# giraffe12.net
KiCad netlist of a schematic drawn in EAGLE
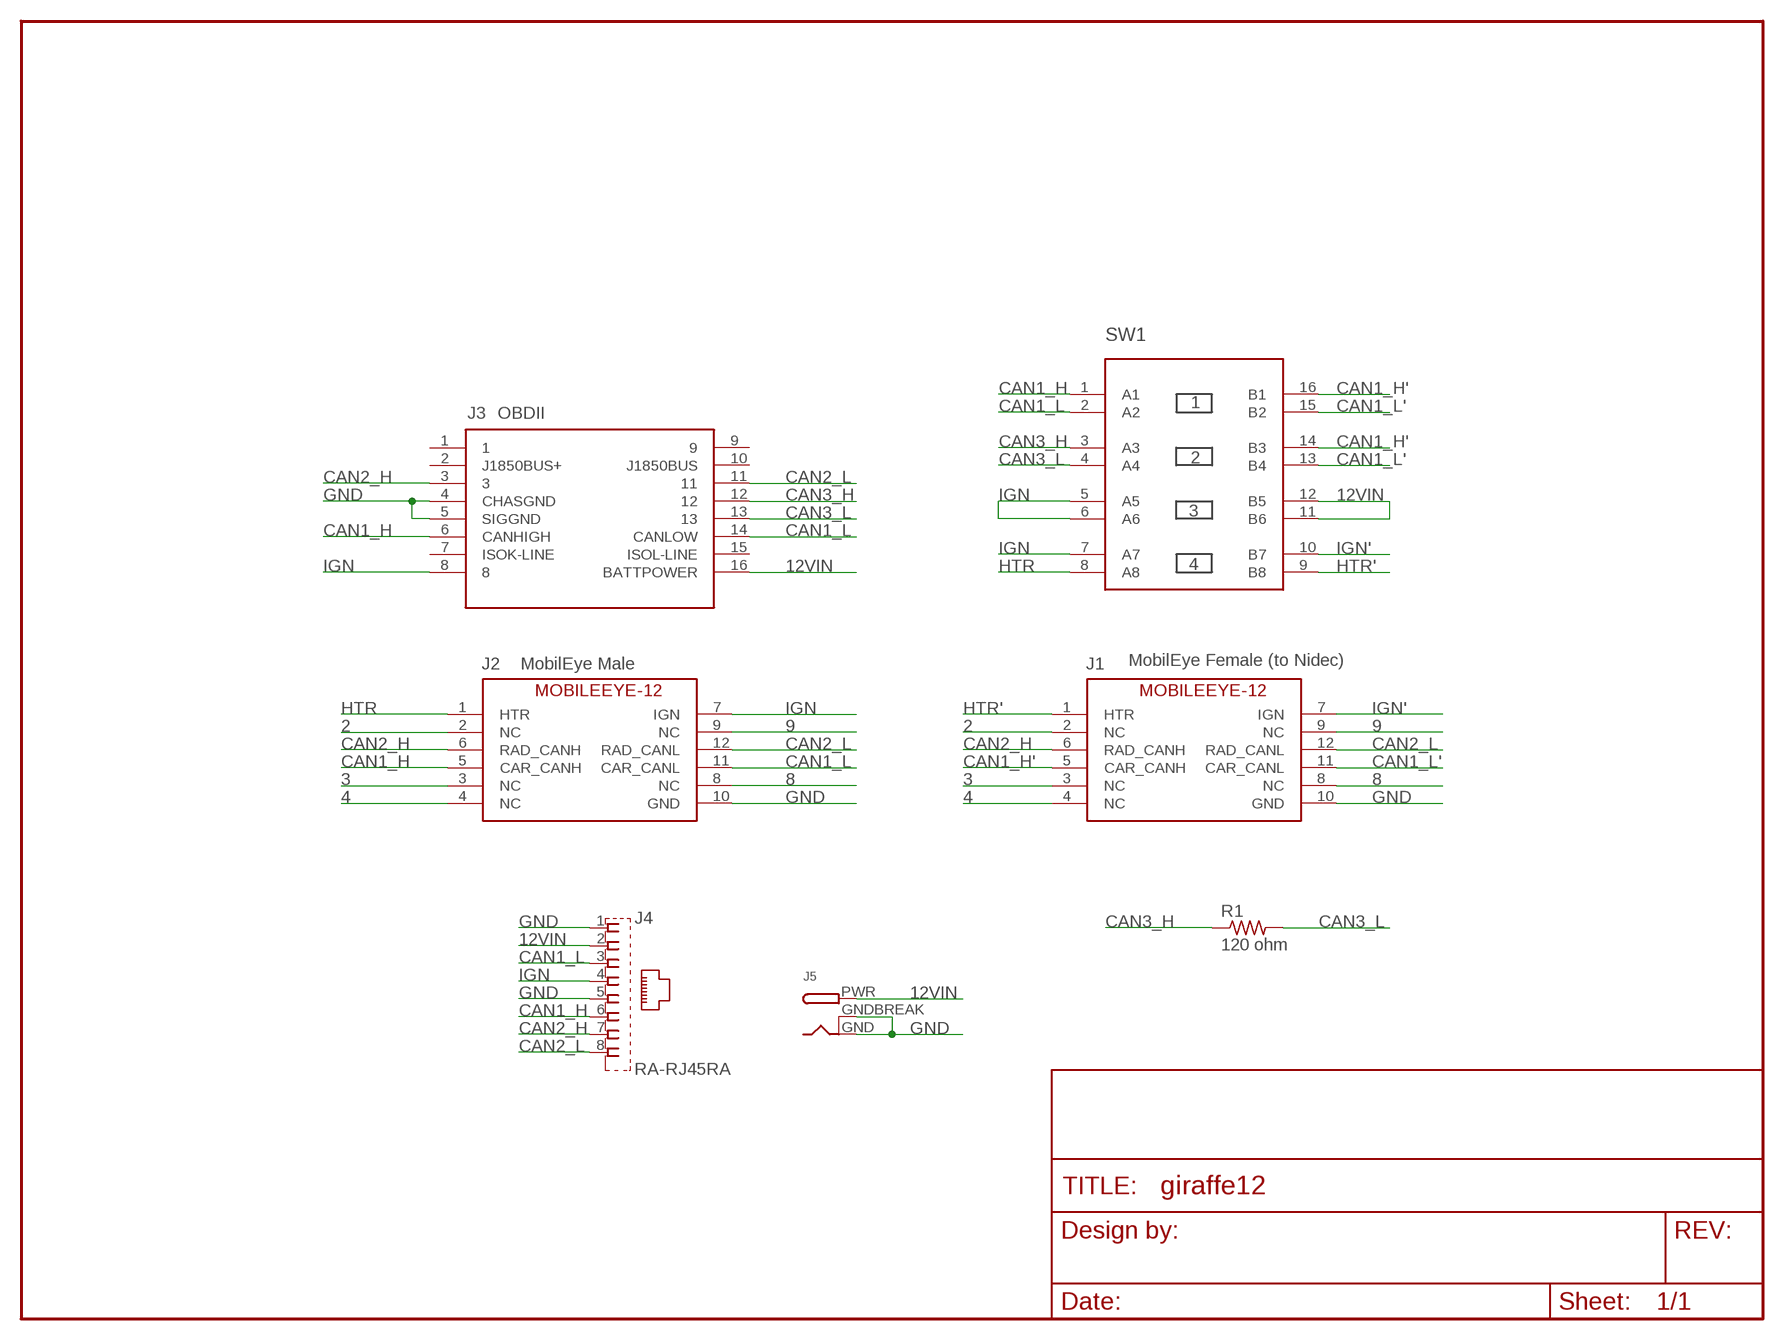
[diagram p0: schematic, sheet 1]

(export (version "E")
  (design (tool "Eeschema 10.0.6"))
  (components
    (comp (ref "FRAME1")
      (value "FRAME-LETTERNO_PACKAGE")
      (footprint "eagle-import:DUMMY")
      (fields (field (name "DESIGNER") "Nobody"))
      (libsource (lib "eagle-import") (part "FRAME-LETTERNO_PACKAGE"))
    )
    (comp (ref "J1")
      (value "MOBILEEYE-12FEMALE")
      (footprint "eagle-import:2X6-TE-FEMALE")
      (libsource (lib "eagle-import") (part "MOBILEEYE-12FEMALE"))
    )
    (comp (ref "J2")
      (value "MOBILEEYE-12MALE")
      (footprint "eagle-import:2X6-TE-RA")
      (libsource (lib "eagle-import") (part "MOBILEEYE-12MALE"))
    )
    (comp (ref "J3")
      (value "OBDII-FEMALE-CUT")
      (footprint "eagle-import:OBDII-FEMALE-MIDCUT")
      (libsource (lib "eagle-import") (part "OBDII-FEMALE-CUT"))
    )
    (comp (ref "J4")
      (value "RA-RJ45RA")
      (footprint "eagle-import:RA-RJ45")
      (libsource (lib "eagle-import") (part "RA-RJ45RA"))
    )
    (comp (ref "J5")
      (value "DCBARRELPTH")
      (footprint "eagle-import:DCJACK_2MM_PTH")
      (libsource (lib "eagle-import") (part "DCBARRELPTH"))
    )
    (comp (ref "R1")
      (value "120 ohm")
      (footprint "eagle-import:0603-R")
      (libsource (lib "eagle-import") (part "R0603"))
    )
    (comp (ref "SW1")
      (value "4XDPSTSMT")
      (footprint "eagle-import:4-DPST")
      (libsource (lib "eagle-import") (part "4XDPSTSMT"))
    )
  )
  (nets
    (net (code "1") (name "/2") (class "Default")
      (node (ref "J1") (pin "2") (pinfunction "NC_2") (pintype "bidirectional"))
      (node (ref "J2") (pin "2") (pinfunction "NC_2") (pintype "bidirectional"))
    )
    (net (code "2") (name "/3") (class "Default")
      (node (ref "J1") (pin "3") (pinfunction "NC_3") (pintype "bidirectional"))
      (node (ref "J2") (pin "3") (pinfunction "NC_3") (pintype "bidirectional"))
    )
    (net (code "3") (name "/4") (class "Default")
      (node (ref "J1") (pin "4") (pinfunction "NC_4") (pintype "bidirectional"))
      (node (ref "J2") (pin "4") (pinfunction "NC_4") (pintype "bidirectional"))
    )
    (net (code "4") (name "/8") (class "Default")
      (node (ref "J1") (pin "8") (pinfunction "NC_8") (pintype "bidirectional"))
      (node (ref "J2") (pin "8") (pinfunction "NC_8") (pintype "bidirectional"))
    )
    (net (code "5") (name "/9") (class "Default")
      (node (ref "J1") (pin "9") (pinfunction "NC_9") (pintype "bidirectional"))
      (node (ref "J2") (pin "9") (pinfunction "NC_9") (pintype "bidirectional"))
    )
    (net (code "6") (name "/12VIN") (class "Default")
      (node (ref "J3") (pin "16") (pinfunction "BATTPOWER_16") (pintype "bidirectional"))
      (node (ref "J4") (pin "2") (pinfunction "2_2") (pintype "passive"))
      (node (ref "J5") (pin "PWR") (pinfunction "PWR_PWR") (pintype "power_in"))
      (node (ref "SW1") (pin "11") (pinfunction "B6_11") (pintype "bidirectional"))
      (node (ref "SW1") (pin "12") (pinfunction "B5_12") (pintype "bidirectional"))
    )
    (net (code "7") (name "/CAN1_H") (class "Default")
      (node (ref "J2") (pin "5") (pinfunction "CAR_CANH_5") (pintype "bidirectional"))
      (node (ref "J3") (pin "6") (pinfunction "CANHIGH_6") (pintype "bidirectional"))
      (node (ref "J4") (pin "6") (pinfunction "6_6") (pintype "passive"))
      (node (ref "SW1") (pin "1") (pinfunction "A1_1") (pintype "bidirectional"))
    )
    (net (code "8") (name "/CAN1_H'") (class "Default")
      (node (ref "J1") (pin "5") (pinfunction "CAR_CANH_5") (pintype "bidirectional"))
      (node (ref "SW1") (pin "14") (pinfunction "B3_14") (pintype "bidirectional"))
      (node (ref "SW1") (pin "16") (pinfunction "B1_16") (pintype "bidirectional"))
    )
    (net (code "9") (name "/CAN1_L") (class "Default")
      (node (ref "J2") (pin "11") (pinfunction "CAR_CANL_11") (pintype "bidirectional"))
      (node (ref "J3") (pin "14") (pinfunction "CANLOW_14") (pintype "bidirectional"))
      (node (ref "J4") (pin "3") (pinfunction "3_3") (pintype "passive"))
      (node (ref "SW1") (pin "2") (pinfunction "A2_2") (pintype "bidirectional"))
    )
    (net (code "10") (name "/CAN1_L'") (class "Default")
      (node (ref "J1") (pin "11") (pinfunction "CAR_CANL_11") (pintype "bidirectional"))
      (node (ref "SW1") (pin "13") (pinfunction "B4_13") (pintype "bidirectional"))
      (node (ref "SW1") (pin "15") (pinfunction "B2_15") (pintype "bidirectional"))
    )
    (net (code "11") (name "/CAN2_H") (class "Default")
      (node (ref "J1") (pin "6") (pinfunction "RAD_CANH_6") (pintype "bidirectional"))
      (node (ref "J2") (pin "6") (pinfunction "RAD_CANH_6") (pintype "bidirectional"))
      (node (ref "J3") (pin "3") (pinfunction "3_3") (pintype "bidirectional"))
      (node (ref "J4") (pin "7") (pinfunction "7_7") (pintype "passive"))
    )
    (net (code "12") (name "/CAN2_L") (class "Default")
      (node (ref "J1") (pin "12") (pinfunction "RAD_CANL_12") (pintype "bidirectional"))
      (node (ref "J2") (pin "12") (pinfunction "RAD_CANL_12") (pintype "bidirectional"))
      (node (ref "J3") (pin "11") (pinfunction "11_11") (pintype "bidirectional"))
      (node (ref "J4") (pin "8") (pinfunction "8_8") (pintype "passive"))
    )
    (net (code "13") (name "/CAN3_H") (class "Default")
      (node (ref "J3") (pin "12") (pinfunction "12_12") (pintype "bidirectional"))
      (node (ref "R1") (pin "1") (pinfunction "1_1") (pintype "passive"))
      (node (ref "SW1") (pin "3") (pinfunction "A3_3") (pintype "bidirectional"))
    )
    (net (code "14") (name "/CAN3_L") (class "Default")
      (node (ref "J3") (pin "13") (pinfunction "13_13") (pintype "bidirectional"))
      (node (ref "R1") (pin "2") (pinfunction "2_2") (pintype "passive"))
      (node (ref "SW1") (pin "4") (pinfunction "A4_4") (pintype "bidirectional"))
    )
    (net (code "15") (name "/GND") (class "Default")
      (node (ref "J1") (pin "10") (pinfunction "GND_10") (pintype "bidirectional"))
      (node (ref "J2") (pin "10") (pinfunction "GND_10") (pintype "bidirectional"))
      (node (ref "J3") (pin "4") (pinfunction "CHASGND_4") (pintype "bidirectional"))
      (node (ref "J3") (pin "5") (pinfunction "SIGGND_5") (pintype "bidirectional"))
      (node (ref "J4") (pin "1") (pinfunction "1_1") (pintype "passive"))
      (node (ref "J4") (pin "5") (pinfunction "5_5") (pintype "passive"))
      (node (ref "J5") (pin "GND") (pinfunction "GND_GND") (pintype "power_in"))
      (node (ref "J5") (pin "GNDBREAK") (pinfunction "GNDBREAK_GNDBREAK") (pintype "power_in"))
    )
    (net (code "16") (name "/HTR") (class "Default")
      (node (ref "J2") (pin "1") (pinfunction "HTR_1") (pintype "bidirectional"))
      (node (ref "SW1") (pin "8") (pinfunction "A8_8") (pintype "bidirectional"))
    )
    (net (code "17") (name "/HTR'") (class "Default")
      (node (ref "J1") (pin "1") (pinfunction "HTR_1") (pintype "bidirectional"))
      (node (ref "SW1") (pin "9") (pinfunction "B8_9") (pintype "bidirectional"))
    )
    (net (code "18") (name "/IGN") (class "Default")
      (node (ref "J2") (pin "7") (pinfunction "IGN_7") (pintype "bidirectional"))
      (node (ref "J3") (pin "8") (pinfunction "8_8") (pintype "bidirectional"))
      (node (ref "J4") (pin "4") (pinfunction "4_4") (pintype "passive"))
      (node (ref "SW1") (pin "5") (pinfunction "A5_5") (pintype "bidirectional"))
      (node (ref "SW1") (pin "6") (pinfunction "A6_6") (pintype "bidirectional"))
      (node (ref "SW1") (pin "7") (pinfunction "A7_7") (pintype "bidirectional"))
    )
    (net (code "19") (name "/IGN'") (class "Default")
      (node (ref "J1") (pin "7") (pinfunction "IGN_7") (pintype "bidirectional"))
      (node (ref "SW1") (pin "10") (pinfunction "B7_10") (pintype "bidirectional"))
    )
    (net (code "20") (name "unconnected-(J3-ISOK-LINE-Pad7)") (class "Default")
      (node (ref "J3") (pin "7") (pinfunction "ISOK-LINE_7") (pintype "bidirectional"))
    )
    (net (code "21") (name "unconnected-(J3-ISOL-LINE-Pad15)") (class "Default")
      (node (ref "J3") (pin "15") (pinfunction "ISOL-LINE_15") (pintype "bidirectional"))
    )
    (net (code "22") (name "unconnected-(J3-J1850BUS+-Pad2)") (class "Default")
      (node (ref "J3") (pin "2") (pinfunction "J1850BUS+_2") (pintype "bidirectional"))
    )
    (net (code "23") (name "unconnected-(J3-J1850BUS-Pad10)") (class "Default")
      (node (ref "J3") (pin "10") (pinfunction "J1850BUS_10") (pintype "bidirectional"))
    )
    (net (code "24") (name "unconnected-(J3-Pad1)") (class "Default")
      (node (ref "J3") (pin "1") (pinfunction "1_1") (pintype "bidirectional"))
    )
    (net (code "25") (name "unconnected-(J3-Pad9)") (class "Default")
      (node (ref "J3") (pin "9") (pinfunction "9_9") (pintype "bidirectional"))
    )
  )
)
